# DCDC_1_Rev2.net
KiCad netlist of a schematic drawn in Altium Designer
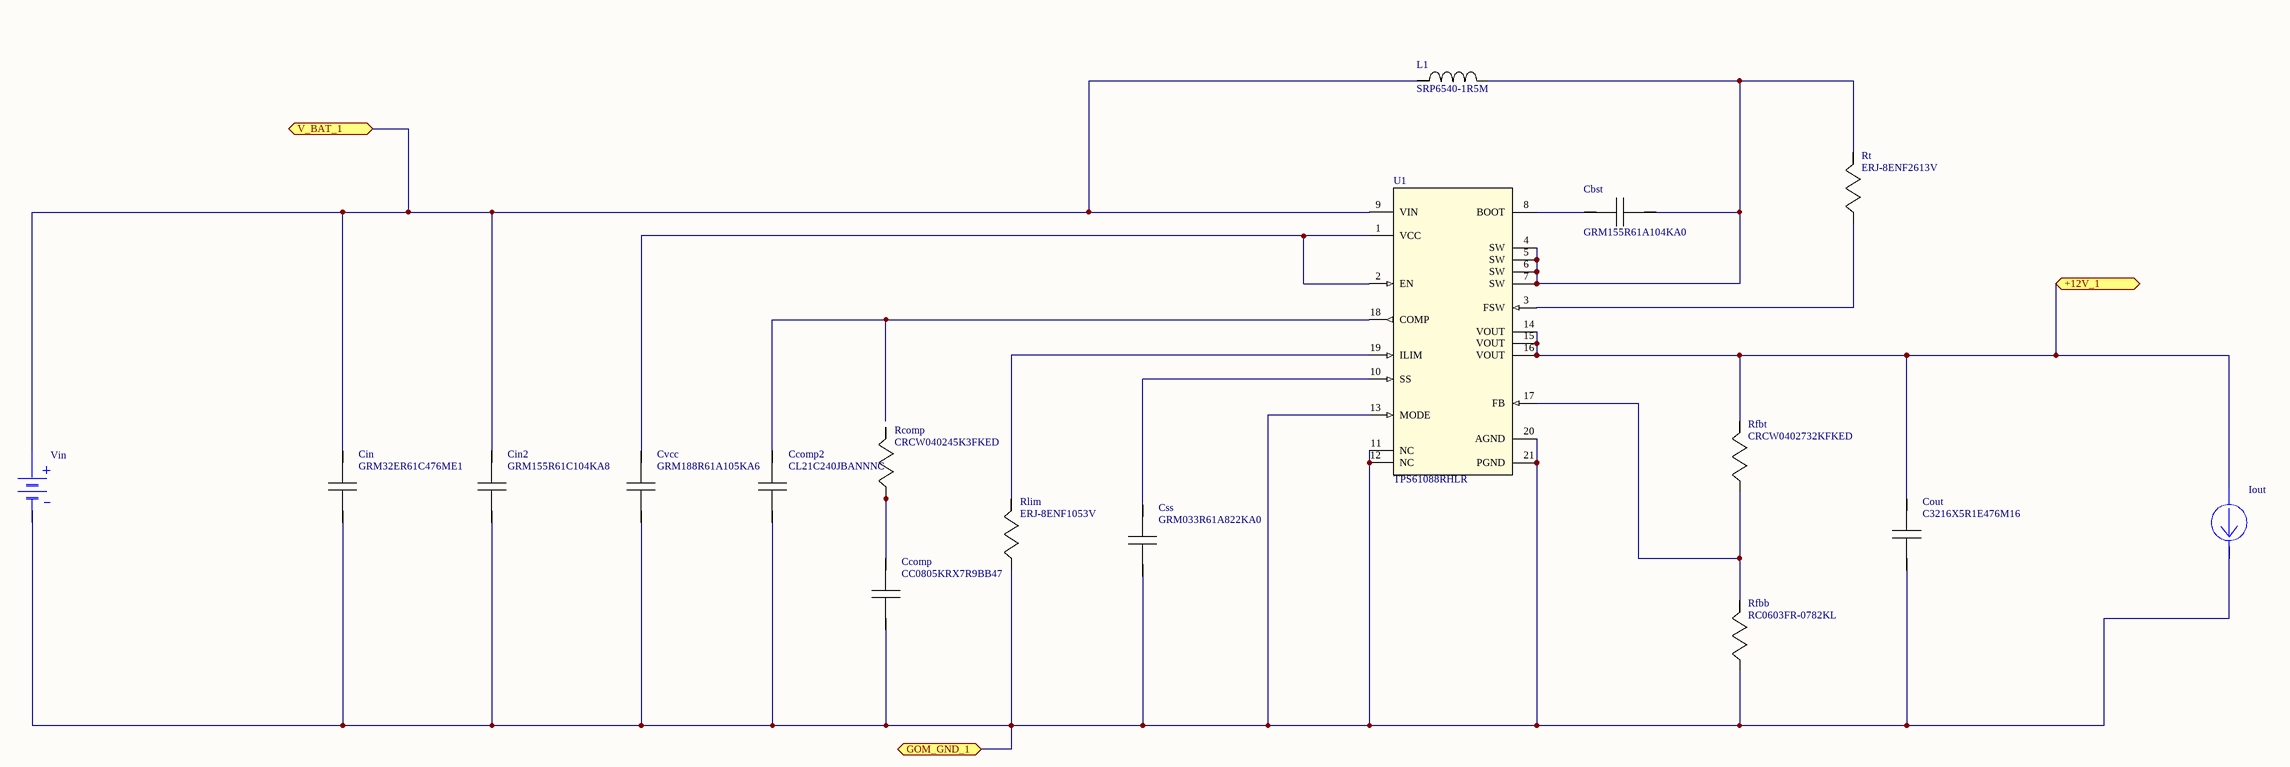
[diagram p0: DCDC_1_Rev2.SchDoc]

(export (version "E")
  (design (tool "Eeschema 10.0.6"))
  (components
    (comp (ref "Cbst")
      (value "GRM155R61A104KA0")
      (footprint "0402")
      (description "Imported")
      (fields (field (name "MANUFACTURER_PART_NUMBER") "GRM155R61A104KA01D"))
      (libsource (lib "2016-03-14_16-10-16") (part "GRM155R61A104KA0"))
    )
    (comp (ref "Ccomp")
      (value "CC0805KRX7R9BB47")
      (footprint "0805")
      (description "Imported")
      (fields (field (name "MANUFACTURER_PART_NUMBER") "CC0805KRX7R9BB471"))
      (libsource (lib "2016-03-14_16-10-16") (part "CC0805KRX7R9BB47"))
    )
    (comp (ref "Ccomp2")
      (value "CL21C240JBANNNC")
      (footprint "0805")
      (description "Imported")
      (libsource (lib "2016-03-14_16-10-16") (part "CL21C240JBANNNC"))
    )
    (comp (ref "Cin")
      (value "GRM32ER61C476ME1")
      (footprint "1210_280")
      (description "Imported")
      (fields (field (name "MANUFACTURER_PART_NUMBER") "GRM32ER61C476ME15L"))
      (libsource (lib "2016-03-14_16-10-16") (part "GRM32ER61C476ME1"))
    )
    (comp (ref "Cin2")
      (value "GRM155R61C104KA8")
      (footprint "0402")
      (description "Imported")
      (fields (field (name "MANUFACTURER_PART_NUMBER") "GRM155R61C104KA88D"))
      (libsource (lib "2016-03-14_16-10-16") (part "GRM155R61C104KA8"))
    )
    (comp (ref "Cout")
      (value "C3216X5R1E476M16")
      (footprint "1206_190")
      (description "Imported")
      (fields (field (name "MANUFACTURER_PART_NUMBER") "C3216X5R1E476M160AC"))
      (libsource (lib "2016-03-14_16-10-16") (part "C3216X5R1E476M16"))
    )
    (comp (ref "Css")
      (value "GRM033R61A822KA0")
      (footprint "0201")
      (description "Imported")
      (fields (field (name "MANUFACTURER_PART_NUMBER") "GRM033R61A822KA01D"))
      (libsource (lib "2016-03-14_16-10-16") (part "GRM033R61A822KA0"))
    )
    (comp (ref "Cvcc")
      (value "GRM188R61A105KA6")
      (footprint "0603")
      (description "Imported")
      (fields (field (name "MANUFACTURER_PART_NUMBER") "GRM188R61A105KA61D"))
      (libsource (lib "2016-03-14_16-10-16") (part "GRM188R61A105KA6"))
    )
    (comp (ref "Iout") (value "WB_CURRENT_LOAD") (libsource (lib "TI WEBENCH") (part "Iout")))
    (comp (ref "L1")
      (value "SRP6540-1R5M")
      (footprint "SRP6540")
      (description "Imported")
      (fields (field (name "MANUFACTURER") "Bourns"))
      (libsource (lib "2016-03-14_16-10-16") (part "SRP6540-1R5M"))
    )
    (comp (ref "Rcomp")
      (value "CRCW040245K3FKED")
      (footprint "0402")
      (description "Imported")
      (libsource (lib "2016-03-14_16-10-16") (part "CRCW040245K3FKED"))
    )
    (comp (ref "Rfbb")
      (value "RC0603FR-0782KL")
      (footprint "0603")
      (description "Imported")
      (libsource (lib "2016-03-14_16-10-16") (part "RC0603FR-0782KL"))
    )
    (comp (ref "Rfbt")
      (value "CRCW0402732KFKED")
      (footprint "0402")
      (description "Imported")
      (libsource (lib "2016-03-14_16-10-16") (part "CRCW0402732KFKED"))
    )
    (comp (ref "Rlim")
      (value "ERJ-8ENF1053V")
      (footprint "1206")
      (description "Imported")
      (libsource (lib "2016-03-14_16-10-16") (part "ERJ-8ENF1053V"))
    )
    (comp (ref "Rt")
      (value "ERJ-8ENF2613V")
      (footprint "1206")
      (description "Imported")
      (libsource (lib "2016-03-14_16-10-16") (part "ERJ-8ENF2613V"))
    )
    (comp (ref "U1")
      (value "TPS61088RHLR")
      (footprint "RHL0020A")
      (description "Imported")
      (fields
        (field (name "ALTERNATE PARTNUMBER") "TPS61088RHLT")
        (field (name "MANUFACTURER") "Texas Instruments")
      )
      (libsource (lib "2016-03-14_16-10-16") (part "TPS61088RHLR"))
    )
    (comp (ref "Vin") (value "WB_BATTERY") (libsource (lib "TI WEBENCH") (part "Vin")))
  )
  (nets
    (net (code "1") (name "/+12V_1") (class "Default")
      (node (ref "Cout") (pin "1") (pinfunction "1_1") (pintype "passive"))
      (node (ref "Iout") (pin "1") (pinfunction "+_1") (pintype "passive"))
      (node (ref "Rfbt") (pin "1") (pinfunction "1_1") (pintype "passive"))
      (node (ref "U1") (pin "14") (pinfunction "VOUT_14") (pintype "power_in"))
      (node (ref "U1") (pin "15") (pinfunction "VOUT_15") (pintype "power_in"))
      (node (ref "U1") (pin "16") (pinfunction "VOUT_16") (pintype "power_in"))
    )
    (net (code "2") (name "/GOM_GND_1") (class "Default")
      (node (ref "Ccomp") (pin "2") (pinfunction "2_2") (pintype "passive"))
      (node (ref "Ccomp2") (pin "2") (pinfunction "2_2") (pintype "passive"))
      (node (ref "Cin") (pin "2") (pinfunction "2_2") (pintype "passive"))
      (node (ref "Cin2") (pin "2") (pinfunction "2_2") (pintype "passive"))
      (node (ref "Cout") (pin "2") (pinfunction "2_2") (pintype "passive"))
      (node (ref "Css") (pin "2") (pinfunction "2_2") (pintype "passive"))
      (node (ref "Cvcc") (pin "2") (pinfunction "2_2") (pintype "passive"))
      (node (ref "Iout") (pin "2") (pinfunction "-_2") (pintype "passive"))
      (node (ref "Rfbb") (pin "2") (pinfunction "2_2") (pintype "passive"))
      (node (ref "Rlim") (pin "2") (pinfunction "2_2") (pintype "passive"))
      (node (ref "U1") (pin "11") (pinfunction "NC_11") (pintype "passive"))
      (node (ref "U1") (pin "12") (pinfunction "NC_12") (pintype "passive"))
      (node (ref "U1") (pin "13") (pinfunction "MODE_13") (pintype "input"))
      (node (ref "U1") (pin "20") (pinfunction "AGND_20") (pintype "power_in"))
      (node (ref "U1") (pin "21") (pinfunction "PGND_21") (pintype "power_in"))
      (node (ref "Vin") (pin "2") (pinfunction "-_2") (pintype "passive"))
    )
    (net (code "3") (name "/V_BAT_1") (class "Default")
      (node (ref "Cin") (pin "1") (pinfunction "1_1") (pintype "passive"))
      (node (ref "Cin2") (pin "1") (pinfunction "1_1") (pintype "passive"))
      (node (ref "L1") (pin "1") (pinfunction "1_1") (pintype "passive"))
      (node (ref "U1") (pin "9") (pinfunction "VIN_9") (pintype "power_in"))
      (node (ref "Vin") (pin "1") (pinfunction "+_1") (pintype "passive"))
    )
    (net (code "4") (name "Net-(Cbst-Pad1)") (class "Default")
      (node (ref "Cbst") (pin "1") (pinfunction "1_1") (pintype "passive"))
      (node (ref "L1") (pin "2") (pinfunction "2_2") (pintype "passive"))
      (node (ref "Rt") (pin "1") (pinfunction "1_1") (pintype "passive"))
      (node (ref "U1") (pin "4") (pinfunction "SW_4") (pintype "power_in"))
      (node (ref "U1") (pin "5") (pinfunction "SW_5") (pintype "power_in"))
      (node (ref "U1") (pin "6") (pinfunction "SW_6") (pintype "power_in"))
      (node (ref "U1") (pin "7") (pinfunction "SW_7") (pintype "power_in"))
    )
    (net (code "5") (name "Net-(Ccomp-Pad1)") (class "Default")
      (node (ref "Ccomp") (pin "1") (pinfunction "1_1") (pintype "passive"))
      (node (ref "Rcomp") (pin "2") (pinfunction "2_2") (pintype "passive"))
    )
    (net (code "6") (name "Net-(U1-BOOT)") (class "Default")
      (node (ref "Cbst") (pin "2") (pinfunction "2_2") (pintype "passive"))
      (node (ref "U1") (pin "8") (pinfunction "BOOT_8") (pintype "power_in"))
    )
    (net (code "7") (name "Net-(U1-COMP)") (class "Default")
      (node (ref "Ccomp2") (pin "1") (pinfunction "1_1") (pintype "passive"))
      (node (ref "U1") (pin "18") (pinfunction "COMP_18") (pintype "output"))
    )
    (net (code "8") (name "Net-(U1-EN)") (class "Default")
      (node (ref "Cvcc") (pin "1") (pinfunction "1_1") (pintype "passive"))
      (node (ref "U1") (pin "1") (pinfunction "VCC_1") (pintype "power_in"))
      (node (ref "U1") (pin "2") (pinfunction "EN_2") (pintype "input"))
    )
    (net (code "9") (name "Net-(U1-FB)") (class "Default")
      (node (ref "Rfbb") (pin "1") (pinfunction "1_1") (pintype "passive"))
      (node (ref "Rfbt") (pin "2") (pinfunction "2_2") (pintype "passive"))
      (node (ref "U1") (pin "17") (pinfunction "FB_17") (pintype "input"))
    )
    (net (code "10") (name "Net-(U1-FSW)") (class "Default")
      (node (ref "Rt") (pin "2") (pinfunction "2_2") (pintype "passive"))
      (node (ref "U1") (pin "3") (pinfunction "FSW_3") (pintype "input"))
    )
    (net (code "11") (name "Net-(U1-ILIM)") (class "Default")
      (node (ref "Rlim") (pin "1") (pinfunction "1_1") (pintype "passive"))
      (node (ref "U1") (pin "19") (pinfunction "ILIM_19") (pintype "input"))
    )
    (net (code "12") (name "Net-(U1-SS)") (class "Default")
      (node (ref "Css") (pin "1") (pinfunction "1_1") (pintype "passive"))
      (node (ref "U1") (pin "10") (pinfunction "SS_10") (pintype "input"))
    )
    (net (code "13") (name "unconnected-(Rcomp-Pad1)") (class "Default")
      (node (ref "Rcomp") (pin "1") (pinfunction "1_1") (pintype "passive"))
    )
  )
)
